# GateDrivers.net
KiCad netlist of a schematic drawn in Altium Designer
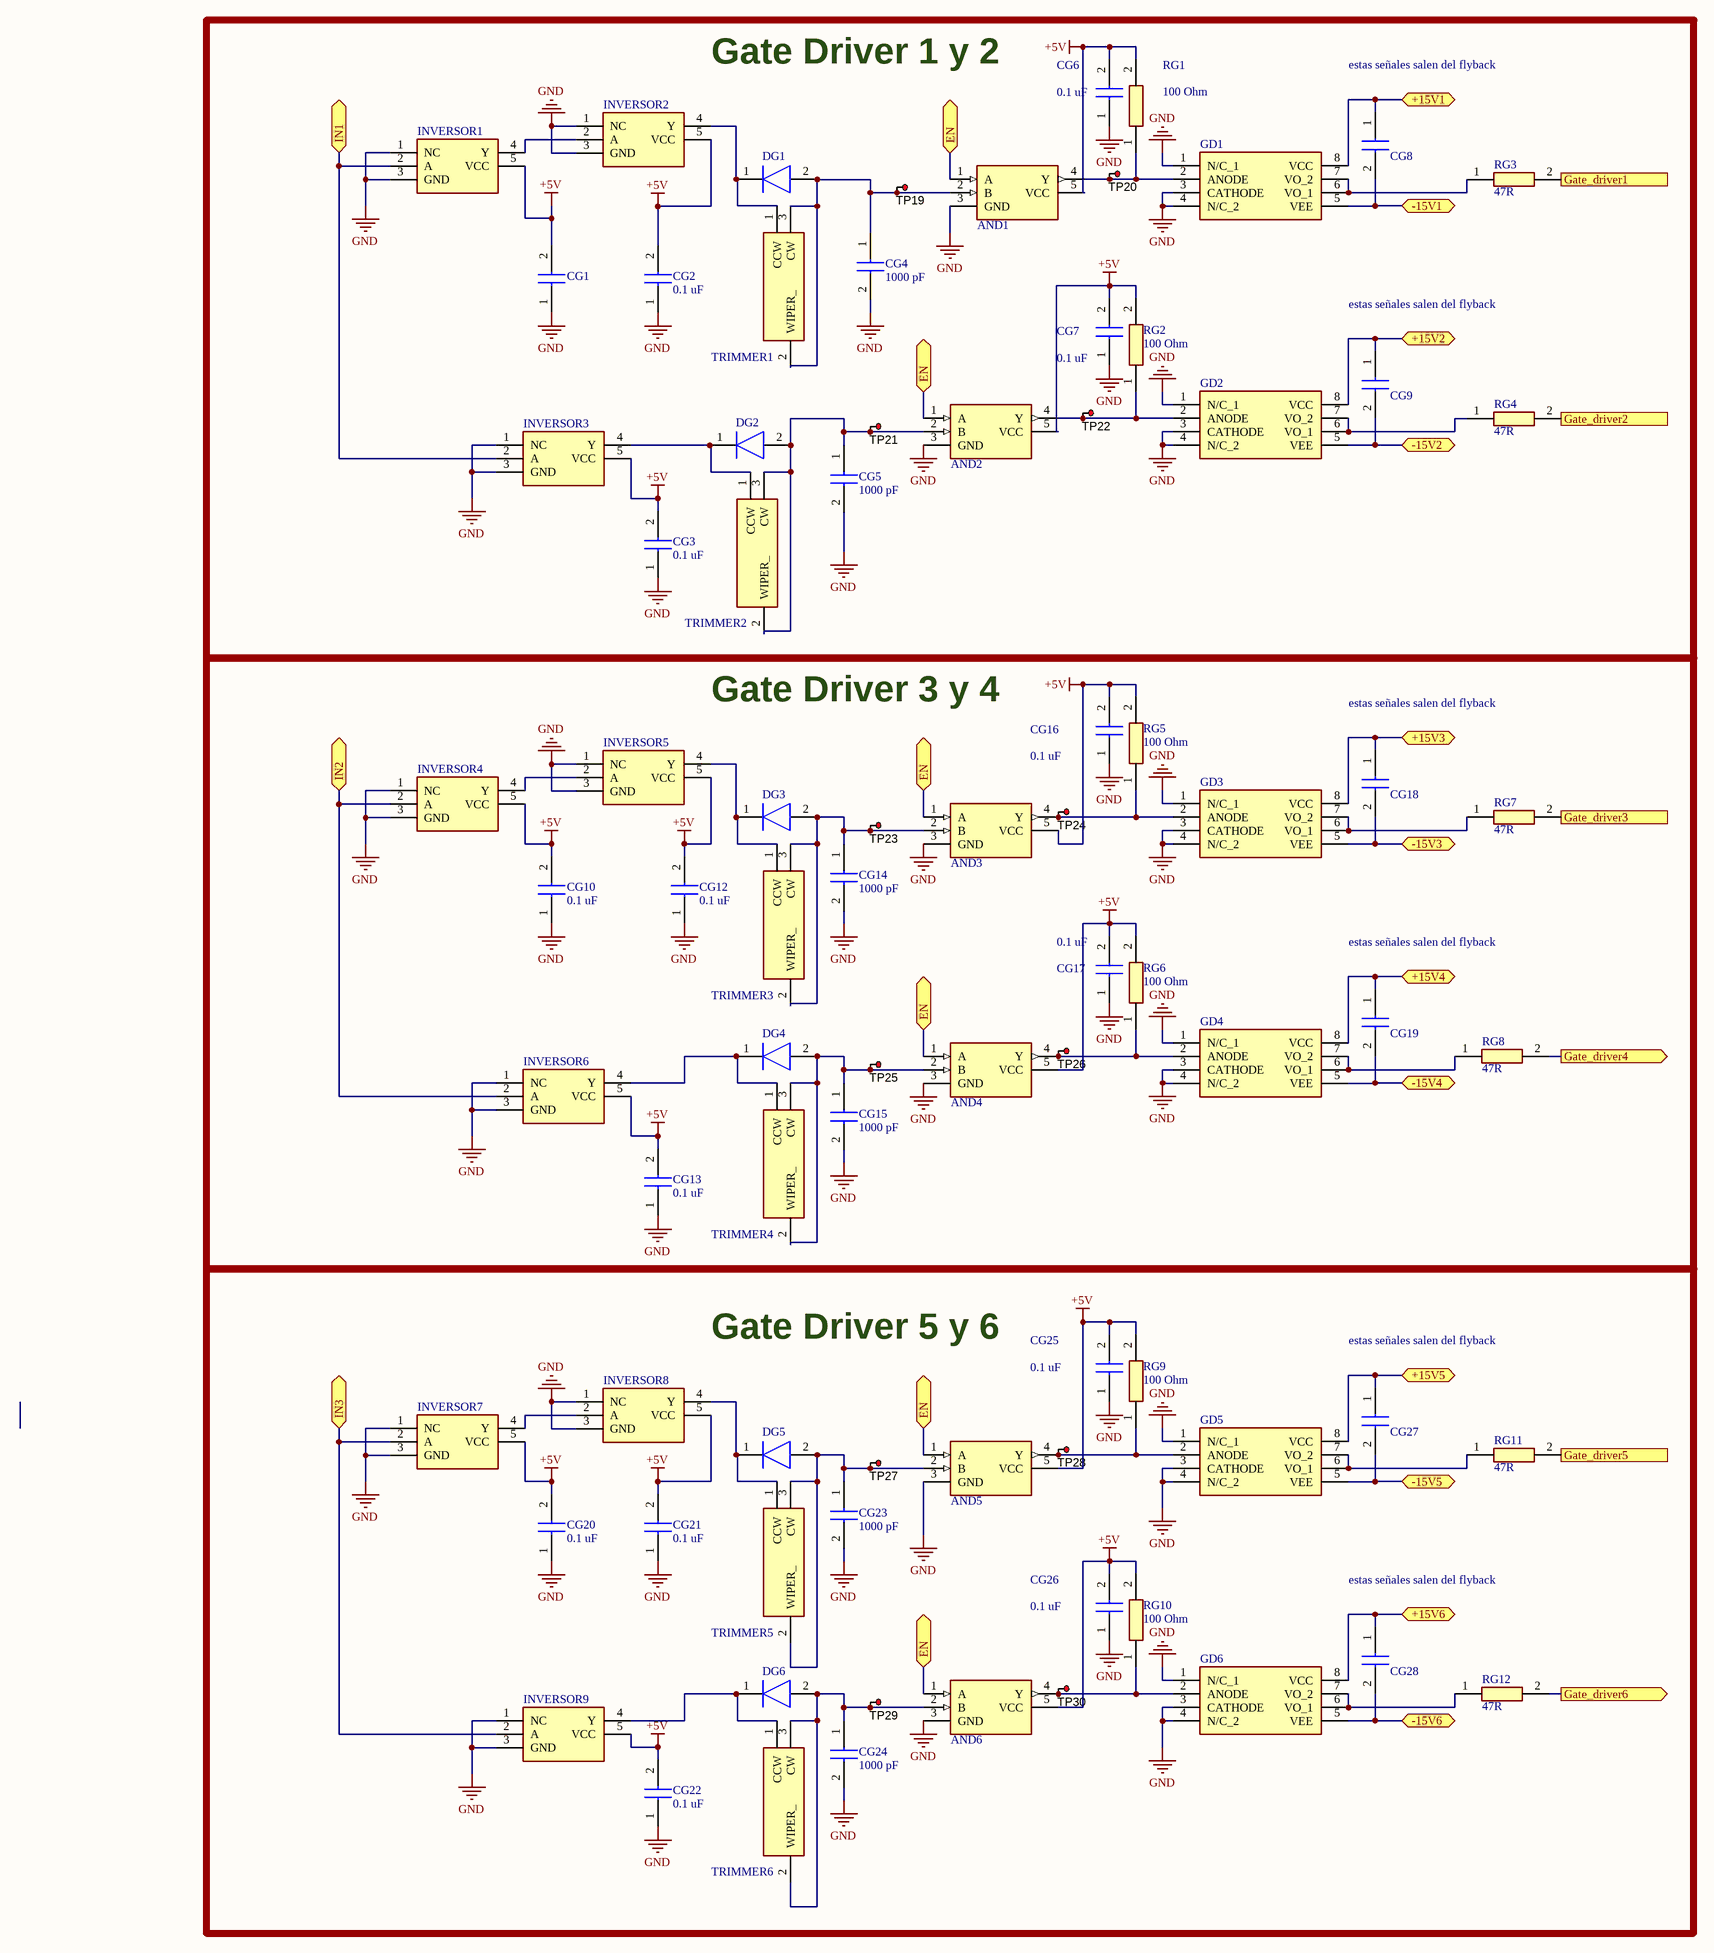
[diagram p0: GateDrivers.SchDoc]

(export (version "E")
  (design (tool "Eeschema 10.0.6"))
  (components
    (comp (ref "AND1")
      (value "SN74AHC1G09DCKR")
      (footprint "jasiel:SOT65P210X110-5N")
      (fields (field (name "MANUFACTURER") "Texas Instruments"))
      (libsource (lib "sch jasiel") (part "SN74AHC1G09DCKR"))
    )
    (comp (ref "AND2")
      (value "SN74AHC1G09DCKR")
      (footprint "jasiel:SOT65P210X110-5N")
      (fields (field (name "MANUFACTURER") "Texas Instruments"))
      (libsource (lib "sch jasiel") (part "SN74AHC1G09DCKR"))
    )
    (comp (ref "AND3")
      (value "SN74AHC1G09DCKR")
      (footprint "jasiel:SOT65P210X110-5N")
      (fields (field (name "MANUFACTURER") "Texas Instruments"))
      (libsource (lib "sch jasiel") (part "SN74AHC1G09DCKR"))
    )
    (comp (ref "AND4")
      (value "SN74AHC1G09DCKR")
      (footprint "jasiel:SOT65P210X110-5N")
      (fields (field (name "MANUFACTURER") "Texas Instruments"))
      (libsource (lib "sch jasiel") (part "SN74AHC1G09DCKR"))
    )
    (comp (ref "AND5")
      (value "SN74AHC1G09DCKR")
      (footprint "jasiel:SOT65P210X110-5N")
      (fields (field (name "MANUFACTURER") "Texas Instruments"))
      (libsource (lib "sch jasiel") (part "SN74AHC1G09DCKR"))
    )
    (comp (ref "AND6")
      (value "SN74AHC1G09DCKR")
      (footprint "jasiel:SOT65P210X110-5N")
      (fields (field (name "MANUFACTURER") "Texas Instruments"))
      (libsource (lib "sch jasiel") (part "SN74AHC1G09DCKR"))
    )
    (comp (ref "CG1")
      (value "~")
      (footprint "SamacSys:CAPC2012X94N")
      (description "Multilayer Ceramic Capacitors MLCC - SMD/SMT 16V .1uF X7R 0805 10%")
      (fields
        (field (name "MANUFACTURER_PART_NUMBER") "0805YC104KAT2A")
        (field (name "MOUSER PART NUMBER") "581-0805YC104K")
      )
      (libsource (lib "sch jasiel") (part "0805YC104KAT2A"))
    )
    (comp (ref "CG2")
      (value "0.1 uF")
      (footprint "SamacSys:CAPC2012X94N")
      (description "Multilayer Ceramic Capacitors MLCC - SMD/SMT 16V .1uF X7R 0805 10%")
      (fields
        (field (name "MANUFACTURER_PART_NUMBER") "0805YC104KAT2A")
        (field (name "MOUSER PART NUMBER") "581-0805YC104K")
      )
      (libsource (lib "*") (part "0805YC104KAT2A"))
    )
    (comp (ref "CG3")
      (value "0.1 uF")
      (footprint "SamacSys:CAPC2012X94N")
      (description "Multilayer Ceramic Capacitors MLCC - SMD/SMT 16V .1uF X7R 0805 10%")
      (fields
        (field (name "MANUFACTURER_PART_NUMBER") "0805YC104KAT2A")
        (field (name "MOUSER PART NUMBER") "581-0805YC104K")
      )
      (libsource (lib "*") (part "0805YC104KAT2A"))
    )
    (comp (ref "CG4")
      (value "1000 pF")
      (footprint "SamacSys:CAPC2012X98N")
      (description "Multilayer Ceramic Capacitors MLCC - SMD/SMT 25volts 1000pF 10% X7R")
      (fields
        (field (name "MANUFACTURER_PART_NUMBER") "C0805Y102K3RACTU")
        (field (name "MOUSER PART NUMBER") "80-C0805Y102K3R")
      )
      (libsource (lib "sch jasiel") (part "C0805Y102K3RACTU"))
    )
    (comp (ref "CG5")
      (value "1000 pF")
      (footprint "SamacSys:CAPC2012X98N")
      (description "Multilayer Ceramic Capacitors MLCC - SMD/SMT 25volts 1000pF 10% X7R")
      (fields
        (field (name "MANUFACTURER_PART_NUMBER") "C0805Y102K3RACTU")
        (field (name "MOUSER PART NUMBER") "80-C0805Y102K3R")
      )
      (libsource (lib "sch jasiel") (part "C0805Y102K3RACTU"))
    )
    (comp (ref "CG6")
      (value "0.1 uF")
      (footprint "SamacSys:CAPC2012X94N")
      (description "Multilayer Ceramic Capacitors MLCC - SMD/SMT 16V .1uF X7R 0805 10%")
      (fields
        (field (name "MANUFACTURER_PART_NUMBER") "0805YC104KAT2A")
        (field (name "MOUSER PART NUMBER") "581-0805YC104K")
      )
      (libsource (lib "*") (part "0805YC104KAT2A"))
    )
    (comp (ref "CG7")
      (value "0.1 uF")
      (footprint "SamacSys:CAPC2012X94N")
      (description "Multilayer Ceramic Capacitors MLCC - SMD/SMT 16V .1uF X7R 0805 10%")
      (fields
        (field (name "MANUFACTURER_PART_NUMBER") "0805YC104KAT2A")
        (field (name "MOUSER PART NUMBER") "581-0805YC104K")
      )
      (libsource (lib "*") (part "0805YC104KAT2A"))
    )
    (comp (ref "CG8")
      (value "CGA2B3X7R1V104M050BB_1")
      (footprint "jasiel:CAPC1005X55N")
      (description "Cap Ceramic 0.1uF 35V X7R 20% Pad SMD 0402 125C Automotive T/R")
      (fields
        (field (name "MANUFACTURER_PART_NUMBER") "CGA2B3X7R1V104M050BB")
        (field (name "MANUFACTURER") "TDK")
      )
      (libsource (lib "sch jasiel") (part "CGA2B3X7R1V104M050BB_1"))
    )
    (comp (ref "CG9")
      (value "CGA2B3X7R1V104M050BB_1")
      (footprint "jasiel:CAPC1005X55N")
      (description "Cap Ceramic 0.1uF 35V X7R 20% Pad SMD 0402 125C Automotive T/R")
      (fields
        (field (name "MANUFACTURER_PART_NUMBER") "CGA2B3X7R1V104M050BB")
        (field (name "MANUFACTURER") "TDK")
      )
      (libsource (lib "sch jasiel") (part "CGA2B3X7R1V104M050BB_1"))
    )
    (comp (ref "CG10")
      (value "0.1 uF")
      (footprint "SamacSys:CAPC2012X94N")
      (description "Multilayer Ceramic Capacitors MLCC - SMD/SMT 16V .1uF X7R 0805 10%")
      (fields
        (field (name "MANUFACTURER_PART_NUMBER") "0805YC104KAT2A")
        (field (name "MOUSER PART NUMBER") "581-0805YC104K")
      )
      (libsource (lib "*") (part "0805YC104KAT2A"))
    )
    (comp (ref "CG12")
      (value "0.1 uF")
      (footprint "SamacSys:CAPC2012X94N")
      (description "Multilayer Ceramic Capacitors MLCC - SMD/SMT 16V .1uF X7R 0805 10%")
      (fields
        (field (name "MANUFACTURER_PART_NUMBER") "0805YC104KAT2A")
        (field (name "MOUSER PART NUMBER") "581-0805YC104K")
      )
      (libsource (lib "*") (part "0805YC104KAT2A"))
    )
    (comp (ref "CG13")
      (value "0.1 uF")
      (footprint "SamacSys:CAPC2012X94N")
      (description "Multilayer Ceramic Capacitors MLCC - SMD/SMT 16V .1uF X7R 0805 10%")
      (fields
        (field (name "MANUFACTURER_PART_NUMBER") "0805YC104KAT2A")
        (field (name "MOUSER PART NUMBER") "581-0805YC104K")
      )
      (libsource (lib "*") (part "0805YC104KAT2A"))
    )
    (comp (ref "CG14")
      (value "1000 pF")
      (footprint "SamacSys:CAPC2012X98N")
      (description "Multilayer Ceramic Capacitors MLCC - SMD/SMT 25volts 1000pF 10% X7R")
      (fields
        (field (name "MANUFACTURER_PART_NUMBER") "C0805Y102K3RACTU")
        (field (name "MOUSER PART NUMBER") "80-C0805Y102K3R")
      )
      (libsource (lib "sch jasiel") (part "C0805Y102K3RACTU"))
    )
    (comp (ref "CG15")
      (value "1000 pF")
      (footprint "SamacSys:CAPC2012X98N")
      (description "Multilayer Ceramic Capacitors MLCC - SMD/SMT 25volts 1000pF 10% X7R")
      (fields
        (field (name "MANUFACTURER_PART_NUMBER") "C0805Y102K3RACTU")
        (field (name "MOUSER PART NUMBER") "80-C0805Y102K3R")
      )
      (libsource (lib "sch jasiel") (part "C0805Y102K3RACTU"))
    )
    (comp (ref "CG16")
      (value "0.1 uF")
      (footprint "SamacSys:CAPC2012X94N")
      (description "Multilayer Ceramic Capacitors MLCC - SMD/SMT 16V .1uF X7R 0805 10%")
      (fields
        (field (name "MANUFACTURER_PART_NUMBER") "0805YC104KAT2A")
        (field (name "MOUSER PART NUMBER") "581-0805YC104K")
      )
      (libsource (lib "*") (part "0805YC104KAT2A"))
    )
    (comp (ref "CG17")
      (value "0.1 uF")
      (footprint "SamacSys:CAPC2012X94N")
      (description "Multilayer Ceramic Capacitors MLCC - SMD/SMT 16V .1uF X7R 0805 10%")
      (fields
        (field (name "MANUFACTURER_PART_NUMBER") "0805YC104KAT2A")
        (field (name "MOUSER PART NUMBER") "581-0805YC104K")
      )
      (libsource (lib "*") (part "0805YC104KAT2A"))
    )
    (comp (ref "CG18")
      (value "CGA2B3X7R1V104M050BB_1")
      (footprint "jasiel:CAPC1005X55N")
      (description "Cap Ceramic 0.1uF 35V X7R 20% Pad SMD 0402 125C Automotive T/R")
      (fields
        (field (name "MANUFACTURER_PART_NUMBER") "CGA2B3X7R1V104M050BB")
        (field (name "MANUFACTURER") "TDK")
      )
      (libsource (lib "sch jasiel") (part "CGA2B3X7R1V104M050BB_1"))
    )
    (comp (ref "CG19")
      (value "CGA2B3X7R1V104M050BB_1")
      (footprint "jasiel:CAPC1005X55N")
      (description "Cap Ceramic 0.1uF 35V X7R 20% Pad SMD 0402 125C Automotive T/R")
      (fields
        (field (name "MANUFACTURER_PART_NUMBER") "CGA2B3X7R1V104M050BB")
        (field (name "MANUFACTURER") "TDK")
      )
      (libsource (lib "sch jasiel") (part "CGA2B3X7R1V104M050BB_1"))
    )
    (comp (ref "CG20")
      (value "0.1 uF")
      (footprint "SamacSys:CAPC2012X94N")
      (description "Multilayer Ceramic Capacitors MLCC - SMD/SMT 16V .1uF X7R 0805 10%")
      (fields
        (field (name "MANUFACTURER_PART_NUMBER") "0805YC104KAT2A")
        (field (name "MOUSER PART NUMBER") "581-0805YC104K")
      )
      (libsource (lib "*") (part "0805YC104KAT2A"))
    )
    (comp (ref "CG21")
      (value "0.1 uF")
      (footprint "SamacSys:CAPC2012X94N")
      (description "Multilayer Ceramic Capacitors MLCC - SMD/SMT 16V .1uF X7R 0805 10%")
      (fields
        (field (name "MANUFACTURER_PART_NUMBER") "0805YC104KAT2A")
        (field (name "MOUSER PART NUMBER") "581-0805YC104K")
      )
      (libsource (lib "*") (part "0805YC104KAT2A"))
    )
    (comp (ref "CG22")
      (value "0.1 uF")
      (footprint "SamacSys:CAPC2012X94N")
      (description "Multilayer Ceramic Capacitors MLCC - SMD/SMT 16V .1uF X7R 0805 10%")
      (fields
        (field (name "MANUFACTURER_PART_NUMBER") "0805YC104KAT2A")
        (field (name "MOUSER PART NUMBER") "581-0805YC104K")
      )
      (libsource (lib "*") (part "0805YC104KAT2A"))
    )
    (comp (ref "CG23")
      (value "1000 pF")
      (footprint "SamacSys:CAPC2012X98N")
      (description "Multilayer Ceramic Capacitors MLCC - SMD/SMT 25volts 1000pF 10% X7R")
      (fields
        (field (name "MANUFACTURER_PART_NUMBER") "C0805Y102K3RACTU")
        (field (name "MOUSER PART NUMBER") "80-C0805Y102K3R")
      )
      (libsource (lib "sch jasiel") (part "C0805Y102K3RACTU"))
    )
    (comp (ref "CG24")
      (value "1000 pF")
      (footprint "SamacSys:CAPC2012X98N")
      (description "Multilayer Ceramic Capacitors MLCC - SMD/SMT 25volts 1000pF 10% X7R")
      (fields
        (field (name "MANUFACTURER_PART_NUMBER") "C0805Y102K3RACTU")
        (field (name "MOUSER PART NUMBER") "80-C0805Y102K3R")
      )
      (libsource (lib "sch jasiel") (part "C0805Y102K3RACTU"))
    )
    (comp (ref "CG25")
      (value "0.1 uF")
      (footprint "SamacSys:CAPC2012X94N")
      (description "Multilayer Ceramic Capacitors MLCC - SMD/SMT 16V .1uF X7R 0805 10%")
      (fields
        (field (name "MANUFACTURER_PART_NUMBER") "0805YC104KAT2A")
        (field (name "MOUSER PART NUMBER") "581-0805YC104K")
      )
      (libsource (lib "*") (part "0805YC104KAT2A"))
    )
    (comp (ref "CG26")
      (value "0.1 uF")
      (footprint "SamacSys:CAPC2012X94N")
      (description "Multilayer Ceramic Capacitors MLCC - SMD/SMT 16V .1uF X7R 0805 10%")
      (fields
        (field (name "MANUFACTURER_PART_NUMBER") "0805YC104KAT2A")
        (field (name "MOUSER PART NUMBER") "581-0805YC104K")
      )
      (libsource (lib "*") (part "0805YC104KAT2A"))
    )
    (comp (ref "CG27")
      (value "CGA2B3X7R1V104M050BB_1")
      (footprint "jasiel:CAPC1005X55N")
      (description "Cap Ceramic 0.1uF 35V X7R 20% Pad SMD 0402 125C Automotive T/R")
      (fields
        (field (name "MANUFACTURER_PART_NUMBER") "CGA2B3X7R1V104M050BB")
        (field (name "MANUFACTURER") "TDK")
      )
      (libsource (lib "sch jasiel") (part "CGA2B3X7R1V104M050BB_1"))
    )
    (comp (ref "CG28")
      (value "CGA2B3X7R1V104M050BB_1")
      (footprint "jasiel:CAPC1005X55N")
      (description "Cap Ceramic 0.1uF 35V X7R 20% Pad SMD 0402 125C Automotive T/R")
      (fields
        (field (name "MANUFACTURER_PART_NUMBER") "CGA2B3X7R1V104M050BB")
        (field (name "MANUFACTURER") "TDK")
      )
      (libsource (lib "sch jasiel") (part "CGA2B3X7R1V104M050BB_1"))
    )
    (comp (ref "DG1")
      (value "BAS85-GS08")
      (footprint "jasiel:BAQ33GS08")
      (description "VISHAY - BAS85-GS08 - Small Signal Schottky Diode, Single, 30 V, 200 mA, 800 mV, 600 mA, 125 °C")
      (fields (field (name "MANUFACTURER") "Vishay Semiconductors") (field (name "VOLTAGE") "30V"))
      (libsource (lib "sch jasiel") (part "BAS85-GS08"))
    )
    (comp (ref "DG2")
      (value "BAS85-GS08")
      (footprint "jasiel:BAQ33GS08")
      (description "VISHAY - BAS85-GS08 - Small Signal Schottky Diode, Single, 30 V, 200 mA, 800 mV, 600 mA, 125 °C")
      (fields (field (name "MANUFACTURER") "Vishay Semiconductors") (field (name "VOLTAGE") "30V"))
      (libsource (lib "sch jasiel") (part "BAS85-GS08"))
    )
    (comp (ref "DG3")
      (value "BAS85-GS08")
      (footprint "jasiel:BAQ33GS08")
      (description "VISHAY - BAS85-GS08 - Small Signal Schottky Diode, Single, 30 V, 200 mA, 800 mV, 600 mA, 125 °C")
      (fields (field (name "MANUFACTURER") "Vishay Semiconductors") (field (name "VOLTAGE") "30V"))
      (libsource (lib "sch jasiel") (part "BAS85-GS08"))
    )
    (comp (ref "DG4")
      (value "BAS85-GS08")
      (footprint "jasiel:BAQ33GS08")
      (description "VISHAY - BAS85-GS08 - Small Signal Schottky Diode, Single, 30 V, 200 mA, 800 mV, 600 mA, 125 °C")
      (fields (field (name "MANUFACTURER") "Vishay Semiconductors") (field (name "VOLTAGE") "30V"))
      (libsource (lib "sch jasiel") (part "BAS85-GS08"))
    )
    (comp (ref "DG5")
      (value "BAS85-GS08")
      (footprint "jasiel:BAQ33GS08")
      (description "VISHAY - BAS85-GS08 - Small Signal Schottky Diode, Single, 30 V, 200 mA, 800 mV, 600 mA, 125 °C")
      (fields (field (name "MANUFACTURER") "Vishay Semiconductors") (field (name "VOLTAGE") "30V"))
      (libsource (lib "sch jasiel") (part "BAS85-GS08"))
    )
    (comp (ref "DG6")
      (value "BAS85-GS08")
      (footprint "jasiel:BAQ33GS08")
      (description "VISHAY - BAS85-GS08 - Small Signal Schottky Diode, Single, 30 V, 200 mA, 800 mV, 600 mA, 125 °C")
      (fields (field (name "MANUFACTURER") "Vishay Semiconductors") (field (name "VOLTAGE") "30V"))
      (libsource (lib "sch jasiel") (part "BAS85-GS08"))
    )
    (comp (ref "GD1")
      (value "HCPL-3120")
      (footprint "jasiel:DIP762W65P254L965H470Q8N")
      (description "Optocoupler Drive Push-Pull 1-CH 30V 1500V 8-Pin PDIP")
      (fields
        (field (name "MOUSER2 PART NUMBER") "630-HCPL-3120")
        (field (name "MANUFACTURER") "Broadcom Avago")
      )
      (libsource (lib "sch jasiel") (part "HCPL-3120"))
    )
    (comp (ref "GD2")
      (value "HCPL-3120")
      (footprint "jasiel:DIP762W65P254L965H470Q8N")
      (description "Optocoupler Drive Push-Pull 1-CH 30V 1500V 8-Pin PDIP")
      (fields
        (field (name "MOUSER2 PART NUMBER") "630-HCPL-3120")
        (field (name "MANUFACTURER") "Broadcom Avago")
      )
      (libsource (lib "sch jasiel") (part "HCPL-3120"))
    )
    (comp (ref "GD3")
      (value "HCPL-3120")
      (footprint "jasiel:DIP762W65P254L965H470Q8N")
      (description "Optocoupler Drive Push-Pull 1-CH 30V 1500V 8-Pin PDIP")
      (fields
        (field (name "MOUSER2 PART NUMBER") "630-HCPL-3120")
        (field (name "MANUFACTURER") "Broadcom Avago")
      )
      (libsource (lib "sch jasiel") (part "HCPL-3120"))
    )
    (comp (ref "GD4")
      (value "HCPL-3120")
      (footprint "jasiel:DIP762W65P254L965H470Q8N")
      (description "Optocoupler Drive Push-Pull 1-CH 30V 1500V 8-Pin PDIP")
      (fields
        (field (name "MOUSER2 PART NUMBER") "630-HCPL-3120")
        (field (name "MANUFACTURER") "Broadcom Avago")
      )
      (libsource (lib "sch jasiel") (part "HCPL-3120"))
    )
    (comp (ref "GD5")
      (value "HCPL-3120")
      (footprint "jasiel:DIP762W65P254L965H470Q8N")
      (description "Optocoupler Drive Push-Pull 1-CH 30V 1500V 8-Pin PDIP")
      (fields
        (field (name "MOUSER2 PART NUMBER") "630-HCPL-3120")
        (field (name "MANUFACTURER") "Broadcom Avago")
      )
      (libsource (lib "sch jasiel") (part "HCPL-3120"))
    )
    (comp (ref "GD6")
      (value "HCPL-3120")
      (footprint "jasiel:DIP762W65P254L965H470Q8N")
      (description "Optocoupler Drive Push-Pull 1-CH 30V 1500V 8-Pin PDIP")
      (fields
        (field (name "MOUSER2 PART NUMBER") "630-HCPL-3120")
        (field (name "MANUFACTURER") "Broadcom Avago")
      )
      (libsource (lib "sch jasiel") (part "HCPL-3120"))
    )
    (comp (ref "INVERSOR1")
      (value "SN74AHC1G14DRLR")
      (footprint "SamacSys:SOTFL50P160X60-5N")
      (description "IC INVERTER SCHMITT 1CH SOT5")
      (fields
        (field (name "MOUSER2 PART NUMBER") "595-SN74AHC1G14DRLR")
        (field (name "MANUFACTURER") "Texas Instruments")
      )
      (libsource (lib "sch jasiel") (part "SN74AHC1G14DRLR"))
    )
    (comp (ref "INVERSOR2")
      (value "SN74AHC1G14DRLR")
      (footprint "SamacSys:SOTFL50P160X60-5N")
      (description "IC INVERTER SCHMITT 1CH SOT5")
      (fields
        (field (name "MOUSER2 PART NUMBER") "595-SN74AHC1G14DRLR")
        (field (name "MANUFACTURER") "Texas Instruments")
      )
      (libsource (lib "sch jasiel") (part "SN74AHC1G14DRLR"))
    )
    (comp (ref "INVERSOR3")
      (value "SN74AHC1G14DRLR")
      (footprint "SamacSys:SOTFL50P160X60-5N")
      (description "IC INVERTER SCHMITT 1CH SOT5")
      (fields
        (field (name "MOUSER2 PART NUMBER") "595-SN74AHC1G14DRLR")
        (field (name "MANUFACTURER") "Texas Instruments")
      )
      (libsource (lib "sch jasiel") (part "SN74AHC1G14DRLR"))
    )
    (comp (ref "INVERSOR4")
      (value "SN74AHC1G14DRLR")
      (footprint "SamacSys:SOTFL50P160X60-5N")
      (description "IC INVERTER SCHMITT 1CH SOT5")
      (fields
        (field (name "MOUSER2 PART NUMBER") "595-SN74AHC1G14DRLR")
        (field (name "MANUFACTURER") "Texas Instruments")
      )
      (libsource (lib "sch jasiel") (part "SN74AHC1G14DRLR"))
    )
    (comp (ref "INVERSOR5")
      (value "SN74AHC1G14DRLR")
      (footprint "SamacSys:SOTFL50P160X60-5N")
      (description "IC INVERTER SCHMITT 1CH SOT5")
      (fields
        (field (name "MOUSER2 PART NUMBER") "595-SN74AHC1G14DRLR")
        (field (name "MANUFACTURER") "Texas Instruments")
      )
      (libsource (lib "sch jasiel") (part "SN74AHC1G14DRLR"))
    )
    (comp (ref "INVERSOR6")
      (value "SN74AHC1G14DRLR")
      (footprint "SamacSys:SOTFL50P160X60-5N")
      (description "IC INVERTER SCHMITT 1CH SOT5")
      (fields
        (field (name "MOUSER2 PART NUMBER") "595-SN74AHC1G14DRLR")
        (field (name "MANUFACTURER") "Texas Instruments")
      )
      (libsource (lib "sch jasiel") (part "SN74AHC1G14DRLR"))
    )
    (comp (ref "INVERSOR7")
      (value "SN74AHC1G14DRLR")
      (footprint "SamacSys:SOTFL50P160X60-5N")
      (description "IC INVERTER SCHMITT 1CH SOT5")
      (fields
        (field (name "MOUSER2 PART NUMBER") "595-SN74AHC1G14DRLR")
        (field (name "MANUFACTURER") "Texas Instruments")
      )
      (libsource (lib "sch jasiel") (part "SN74AHC1G14DRLR"))
    )
    (comp (ref "INVERSOR8")
      (value "SN74AHC1G14DRLR")
      (footprint "SamacSys:SOTFL50P160X60-5N")
      (description "IC INVERTER SCHMITT 1CH SOT5")
      (fields
        (field (name "MOUSER2 PART NUMBER") "595-SN74AHC1G14DRLR")
        (field (name "MANUFACTURER") "Texas Instruments")
      )
      (libsource (lib "sch jasiel") (part "SN74AHC1G14DRLR"))
    )
    (comp (ref "INVERSOR9")
      (value "SN74AHC1G14DRLR")
      (footprint "SamacSys:SOTFL50P160X60-5N")
      (description "IC INVERTER SCHMITT 1CH SOT5")
      (fields
        (field (name "MOUSER2 PART NUMBER") "595-SN74AHC1G14DRLR")
        (field (name "MANUFACTURER") "Texas Instruments")
      )
      (libsource (lib "sch jasiel") (part "SN74AHC1G14DRLR"))
    )
    (comp (ref "RG1")
      (value "100 Ohm")
      (footprint "jasiel:RESC1608X55N")
      (description "YAGEO - RC0603JR-13100RL - RES, THICK FILM, 100R, 5%, 0.1W, 0603")
      (fields
        (field (name "MANUFACTURER_PART_NUMBER") "RC0603JR-13100RL")
        (field (name "MANUFACTURER") "Yageo")
      )
      (libsource (lib "sch jasiel") (part "RC0603JR-13100RL"))
    )
    (comp (ref "RG2")
      (value "100 Ohm")
      (footprint "jasiel:RESC1608X55N")
      (description "YAGEO - RC0603JR-13100RL - RES, THICK FILM, 100R, 5%, 0.1W, 0603")
      (fields
        (field (name "MANUFACTURER_PART_NUMBER") "RC0603JR-13100RL")
        (field (name "MANUFACTURER") "Yageo")
      )
      (libsource (lib "sch jasiel") (part "RC0603JR-13100RL"))
    )
    (comp (ref "RG3")
      (value "RCL121847R0JNEK_1")
      (footprint "SamacSys:RESC3246X60N")
      (description "Res Thick Film 1218 47 Ohm 5% 1W ±200ppm/C Pad SMD Automotive T/R")
      (fields
        (field (name "MANUFACTURER_PART_NUMBER") "RCL121847R0JNEK")
        (field (name "MANUFACTURER") "Vishay")
        (field (name "RESISTANCE") "47R")
      )
      (libsource (lib "sch jasiel") (part "RCL121847R0JNEK_1"))
    )
    (comp (ref "RG4")
      (value "RCL121847R0JNEK_1")
      (footprint "SamacSys:RESC3246X60N")
      (description "Res Thick Film 1218 47 Ohm 5% 1W ±200ppm/C Pad SMD Automotive T/R")
      (fields
        (field (name "MANUFACTURER_PART_NUMBER") "RCL121847R0JNEK")
        (field (name "MANUFACTURER") "Vishay")
        (field (name "RESISTANCE") "47R")
      )
      (libsource (lib "sch jasiel") (part "RCL121847R0JNEK_1"))
    )
    (comp (ref "RG5")
      (value "100 Ohm")
      (footprint "jasiel:RESC1608X55N")
      (description "YAGEO - RC0603JR-13100RL - RES, THICK FILM, 100R, 5%, 0.1W, 0603")
      (fields
        (field (name "MANUFACTURER_PART_NUMBER") "RC0603JR-13100RL")
        (field (name "MANUFACTURER") "Yageo")
      )
      (libsource (lib "sch jasiel") (part "RC0603JR-13100RL"))
    )
    (comp (ref "RG6")
      (value "100 Ohm")
      (footprint "jasiel:RESC1608X55N")
      (description "YAGEO - RC0603JR-13100RL - RES, THICK FILM, 100R, 5%, 0.1W, 0603")
      (fields
        (field (name "MANUFACTURER_PART_NUMBER") "RC0603JR-13100RL")
        (field (name "MANUFACTURER") "Yageo")
      )
      (libsource (lib "sch jasiel") (part "RC0603JR-13100RL"))
    )
    (comp (ref "RG7")
      (value "RCL121847R0JNEK_1")
      (footprint "SamacSys:RESC3246X60N")
      (description "Res Thick Film 1218 47 Ohm 5% 1W ±200ppm/C Pad SMD Automotive T/R")
      (fields
        (field (name "MANUFACTURER_PART_NUMBER") "RCL121847R0JNEK")
        (field (name "MANUFACTURER") "Vishay")
        (field (name "RESISTANCE") "47R")
      )
      (libsource (lib "sch jasiel") (part "RCL121847R0JNEK_1"))
    )
    (comp (ref "RG8")
      (value "RCL121847R0JNEK_1")
      (footprint "SamacSys:RESC3246X60N")
      (description "Res Thick Film 1218 47 Ohm 5% 1W ±200ppm/C Pad SMD Automotive T/R")
      (fields
        (field (name "MANUFACTURER_PART_NUMBER") "RCL121847R0JNEK")
        (field (name "MANUFACTURER") "Vishay")
        (field (name "RESISTANCE") "47R")
      )
      (libsource (lib "sch jasiel") (part "RCL121847R0JNEK_1"))
    )
    (comp (ref "RG9")
      (value "100 Ohm")
      (footprint "jasiel:RESC1608X55N")
      (description "YAGEO - RC0603JR-13100RL - RES, THICK FILM, 100R, 5%, 0.1W, 0603")
      (fields
        (field (name "MANUFACTURER_PART_NUMBER") "RC0603JR-13100RL")
        (field (name "MANUFACTURER") "Yageo")
      )
      (libsource (lib "sch jasiel") (part "RC0603JR-13100RL"))
    )
    (comp (ref "RG10")
      (value "100 Ohm")
      (footprint "jasiel:RESC1608X55N")
      (description "YAGEO - RC0603JR-13100RL - RES, THICK FILM, 100R, 5%, 0.1W, 0603")
      (fields
        (field (name "MANUFACTURER_PART_NUMBER") "RC0603JR-13100RL")
        (field (name "MANUFACTURER") "Yageo")
      )
      (libsource (lib "sch jasiel") (part "RC0603JR-13100RL"))
    )
    (comp (ref "RG11")
      (value "RCL121847R0JNEK_1")
      (footprint "SamacSys:RESC3246X60N")
      (description "Res Thick Film 1218 47 Ohm 5% 1W ±200ppm/C Pad SMD Automotive T/R")
      (fields
        (field (name "MANUFACTURER_PART_NUMBER") "RCL121847R0JNEK")
        (field (name "MANUFACTURER") "Vishay")
        (field (name "RESISTANCE") "47R")
      )
      (libsource (lib "sch jasiel") (part "RCL121847R0JNEK_1"))
    )
    (comp (ref "RG12")
      (value "RCL121847R0JNEK_1")
      (footprint "SamacSys:RESC3246X60N")
      (description "Res Thick Film 1218 47 Ohm 5% 1W ±200ppm/C Pad SMD Automotive T/R")
      (fields
        (field (name "MANUFACTURER_PART_NUMBER") "RCL121847R0JNEK")
        (field (name "MANUFACTURER") "Vishay")
        (field (name "RESISTANCE") "47R")
      )
      (libsource (lib "sch jasiel") (part "RCL121847R0JNEK_1"))
    )
    (comp (ref "TP19")
      (value "5010")
      (footprint "Keystone5010")
      (description "Test Point, Multipurpose, Red, TH")
      (fields (field (name "MANUFACTURER") "Keystone") (field (name "PUBLISHER") "Texas Instruments"))
      (libsource (lib "sch jasiel") (part "5010"))
    )
    (comp (ref "TP20")
      (value "5010")
      (footprint "Keystone5010")
      (description "Test Point, Multipurpose, Red, TH")
      (fields (field (name "MANUFACTURER") "Keystone") (field (name "PUBLISHER") "Texas Instruments"))
      (libsource (lib "sch jasiel") (part "5010"))
    )
    (comp (ref "TP21")
      (value "5010")
      (footprint "Keystone5010")
      (description "Test Point, Multipurpose, Red, TH")
      (fields (field (name "MANUFACTURER") "Keystone") (field (name "PUBLISHER") "Texas Instruments"))
      (libsource (lib "sch jasiel") (part "5010"))
    )
    (comp (ref "TP22")
      (value "5010")
      (footprint "Keystone5010")
      (description "Test Point, Multipurpose, Red, TH")
      (fields (field (name "MANUFACTURER") "Keystone") (field (name "PUBLISHER") "Texas Instruments"))
      (libsource (lib "sch jasiel") (part "5010"))
    )
    (comp (ref "TP23")
      (value "5010")
      (footprint "Keystone5010")
      (description "Test Point, Multipurpose, Red, TH")
      (fields (field (name "MANUFACTURER") "Keystone") (field (name "PUBLISHER") "Texas Instruments"))
      (libsource (lib "sch jasiel") (part "5010"))
    )
    (comp (ref "TP24")
      (value "5010")
      (footprint "Keystone5010")
      (description "Test Point, Multipurpose, Red, TH")
      (fields (field (name "MANUFACTURER") "Keystone") (field (name "PUBLISHER") "Texas Instruments"))
      (libsource (lib "sch jasiel") (part "5010"))
    )
    (comp (ref "TP25")
      (value "5010")
      (footprint "Keystone5010")
      (description "Test Point, Multipurpose, Red, TH")
      (fields (field (name "MANUFACTURER") "Keystone") (field (name "PUBLISHER") "Texas Instruments"))
      (libsource (lib "sch jasiel") (part "5010"))
    )
    (comp (ref "TP26")
      (value "5010")
      (footprint "Keystone5010")
      (description "Test Point, Multipurpose, Red, TH")
      (fields (field (name "MANUFACTURER") "Keystone") (field (name "PUBLISHER") "Texas Instruments"))
      (libsource (lib "sch jasiel") (part "5010"))
    )
    (comp (ref "TP27")
      (value "5010")
      (footprint "Keystone5010")
      (description "Test Point, Multipurpose, Red, TH")
      (fields (field (name "MANUFACTURER") "Keystone") (field (name "PUBLISHER") "Texas Instruments"))
      (libsource (lib "sch jasiel") (part "5010"))
    )
    (comp (ref "TP28")
      (value "5010")
      (footprint "Keystone5010")
      (description "Test Point, Multipurpose, Red, TH")
      (fields (field (name "MANUFACTURER") "Keystone") (field (name "PUBLISHER") "Texas Instruments"))
      (libsource (lib "sch jasiel") (part "5010"))
    )
    (comp (ref "TP29")
      (value "5010")
      (footprint "Keystone5010")
      (description "Test Point, Multipurpose, Red, TH")
      (fields (field (name "MANUFACTURER") "Keystone") (field (name "PUBLISHER") "Texas Instruments"))
      (libsource (lib "sch jasiel") (part "5010"))
    )
    (comp (ref "TP30")
      (value "5010")
      (footprint "Keystone5010")
      (description "Test Point, Multipurpose, Red, TH")
      (fields (field (name "MANUFACTURER") "Keystone") (field (name "PUBLISHER") "Texas Instruments"))
      (libsource (lib "sch jasiel") (part "5010"))
    )
    (comp (ref "TRIMMER1")
      (value "ST-4ETB203")
      (footprint "SamacSys:ST4ETB203")
      (description "TRIMMER 20K OHM 0.25W SMD")
      (fields
        (field (name "MANUFACTURER") "Nidec Copal")
        (field (name "MANUFACTURER PART NUMBER") "ST4ETB203")
      )
      (libsource (lib "sch jasiel") (part "ST-4ETB203"))
    )
    (comp (ref "TRIMMER2")
      (value "ST-4ETB203")
      (footprint "SamacSys:ST4ETB203")
      (description "TRIMMER 20K OHM 0.25W SMD")
      (fields
        (field (name "MANUFACTURER") "Nidec Copal")
        (field (name "MANUFACTURER PART NUMBER") "ST4ETB203")
      )
      (libsource (lib "sch jasiel") (part "ST-4ETB203"))
    )
    (comp (ref "TRIMMER3")
      (value "ST-4ETB203")
      (footprint "SamacSys:ST4ETB203")
      (description "TRIMMER 20K OHM 0.25W SMD")
      (fields
        (field (name "MANUFACTURER") "Nidec Copal")
        (field (name "MANUFACTURER PART NUMBER") "ST4ETB203")
      )
      (libsource (lib "sch jasiel") (part "ST-4ETB203"))
    )
    (comp (ref "TRIMMER4")
      (value "ST-4ETB203")
      (footprint "SamacSys:ST4ETB203")
      (description "TRIMMER 20K OHM 0.25W SMD")
      (fields
        (field (name "MANUFACTURER") "Nidec Copal")
        (field (name "MANUFACTURER PART NUMBER") "ST4ETB203")
      )
      (libsource (lib "sch jasiel") (part "ST-4ETB203"))
    )
    (comp (ref "TRIMMER5")
      (value "ST-4ETB203")
      (footprint "SamacSys:ST4ETB203")
      (description "TRIMMER 20K OHM 0.25W SMD")
      (fields
        (field (name "MANUFACTURER") "Nidec Copal")
        (field (name "MANUFACTURER PART NUMBER") "ST4ETB203")
      )
      (libsource (lib "sch jasiel") (part "ST-4ETB203"))
    )
    (comp (ref "TRIMMER6")
      (value "ST-4ETB203")
      (footprint "SamacSys:ST4ETB203")
      (description "TRIMMER 20K OHM 0.25W SMD")
      (fields
        (field (name "MANUFACTURER") "Nidec Copal")
        (field (name "MANUFACTURER PART NUMBER") "ST4ETB203")
      )
      (libsource (lib "sch jasiel") (part "ST-4ETB203"))
    )
  )
  (nets
    (net (code "1") (name "+5V") (class "Default")
      (node (ref "AND1") (pin "5") (pinfunction "VCC_5") (pintype "power_in"))
      (node (ref "AND2") (pin "5") (pinfunction "VCC_5") (pintype "power_in"))
      (node (ref "AND3") (pin "5") (pinfunction "VCC_5") (pintype "power_in"))
      (node (ref "AND4") (pin "5") (pinfunction "VCC_5") (pintype "power_in"))
      (node (ref "AND5") (pin "5") (pinfunction "VCC_5") (pintype "power_in"))
      (node (ref "AND6") (pin "5") (pinfunction "VCC_5") (pintype "power_in"))
      (node (ref "CG1") (pin "2") (pinfunction "2_2") (pintype "passive"))
      (node (ref "CG10") (pin "2") (pinfunction "2_2") (pintype "passive"))
      (node (ref "CG12") (pin "2") (pinfunction "2_2") (pintype "passive"))
      (node (ref "CG13") (pin "2") (pinfunction "2_2") (pintype "passive"))
      (node (ref "CG16") (pin "2") (pinfunction "2_2") (pintype "passive"))
      (node (ref "CG17") (pin "2") (pinfunction "2_2") (pintype "passive"))
      (node (ref "CG2") (pin "2") (pinfunction "2_2") (pintype "passive"))
      (node (ref "CG20") (pin "2") (pinfunction "2_2") (pintype "passive"))
      (node (ref "CG21") (pin "2") (pinfunction "2_2") (pintype "passive"))
      (node (ref "CG22") (pin "2") (pinfunction "2_2") (pintype "passive"))
      (node (ref "CG25") (pin "2") (pinfunction "2_2") (pintype "passive"))
      (node (ref "CG26") (pin "2") (pinfunction "2_2") (pintype "passive"))
      (node (ref "CG3") (pin "2") (pinfunction "2_2") (pintype "passive"))
      (node (ref "CG6") (pin "2") (pinfunction "2_2") (pintype "passive"))
      (node (ref "CG7") (pin "2") (pinfunction "2_2") (pintype "passive"))
      (node (ref "INVERSOR1") (pin "5") (pinfunction "VCC_5") (pintype "passive"))
      (node (ref "INVERSOR2") (pin "5") (pinfunction "VCC_5") (pintype "passive"))
      (node (ref "INVERSOR3") (pin "5") (pinfunction "VCC_5") (pintype "passive"))
      (node (ref "INVERSOR4") (pin "5") (pinfunction "VCC_5") (pintype "passive"))
      (node (ref "INVERSOR5") (pin "5") (pinfunction "VCC_5") (pintype "passive"))
      (node (ref "INVERSOR6") (pin "5") (pinfunction "VCC_5") (pintype "passive"))
      (node (ref "INVERSOR7") (pin "5") (pinfunction "VCC_5") (pintype "passive"))
      (node (ref "INVERSOR8") (pin "5") (pinfunction "VCC_5") (pintype "passive"))
      (node (ref "INVERSOR9") (pin "5") (pinfunction "VCC_5") (pintype "passive"))
      (node (ref "RG1") (pin "2") (pinfunction "2_2") (pintype "passive"))
      (node (ref "RG10") (pin "2") (pinfunction "2_2") (pintype "passive"))
      (node (ref "RG2") (pin "2") (pinfunction "2_2") (pintype "passive"))
      (node (ref "RG5") (pin "2") (pinfunction "2_2") (pintype "passive"))
      (node (ref "RG6") (pin "2") (pinfunction "2_2") (pintype "passive"))
      (node (ref "RG9") (pin "2") (pinfunction "2_2") (pintype "passive"))
    )
    (net (code "2") (name "/+15V1") (class "Default")
      (node (ref "CG8") (pin "1") (pinfunction "1_1") (pintype "passive"))
      (node (ref "GD1") (pin "8") (pinfunction "VCC_8") (pintype "passive"))
    )
    (net (code "3") (name "/+15V2") (class "Default")
      (node (ref "CG9") (pin "1") (pinfunction "1_1") (pintype "passive"))
      (node (ref "GD2") (pin "8") (pinfunction "VCC_8") (pintype "passive"))
    )
    (net (code "4") (name "/+15V3") (class "Default")
      (node (ref "CG18") (pin "1") (pinfunction "1_1") (pintype "passive"))
      (node (ref "GD3") (pin "8") (pinfunction "VCC_8") (pintype "passive"))
    )
    (net (code "5") (name "/+15V4") (class "Default")
      (node (ref "CG19") (pin "1") (pinfunction "1_1") (pintype "passive"))
      (node (ref "GD4") (pin "8") (pinfunction "VCC_8") (pintype "passive"))
    )
    (net (code "6") (name "/+15V5") (class "Default")
      (node (ref "CG27") (pin "1") (pinfunction "1_1") (pintype "passive"))
      (node (ref "GD5") (pin "8") (pinfunction "VCC_8") (pintype "passive"))
    )
    (net (code "7") (name "/+15V6") (class "Default")
      (node (ref "CG28") (pin "1") (pinfunction "1_1") (pintype "passive"))
      (node (ref "GD6") (pin "8") (pinfunction "VCC_8") (pintype "passive"))
    )
    (net (code "8") (name "/-15V1") (class "Default")
      (node (ref "CG8") (pin "2") (pinfunction "2_2") (pintype "passive"))
      (node (ref "GD1") (pin "5") (pinfunction "VEE_5") (pintype "passive"))
    )
    (net (code "9") (name "/-15V2") (class "Default")
      (node (ref "CG9") (pin "2") (pinfunction "2_2") (pintype "passive"))
      (node (ref "GD2") (pin "5") (pinfunction "VEE_5") (pintype "passive"))
    )
    (net (code "10") (name "/-15V3") (class "Default")
      (node (ref "CG18") (pin "2") (pinfunction "2_2") (pintype "passive"))
      (node (ref "GD3") (pin "5") (pinfunction "VEE_5") (pintype "passive"))
    )
    (net (code "11") (name "/-15V4") (class "Default")
      (node (ref "CG19") (pin "2") (pinfunction "2_2") (pintype "passive"))
      (node (ref "GD4") (pin "5") (pinfunction "VEE_5") (pintype "passive"))
    )
    (net (code "12") (name "/-15V5") (class "Default")
      (node (ref "CG27") (pin "2") (pinfunction "2_2") (pintype "passive"))
      (node (ref "GD5") (pin "5") (pinfunction "VEE_5") (pintype "passive"))
    )
    (net (code "13") (name "/-15V6") (class "Default")
      (node (ref "CG28") (pin "2") (pinfunction "2_2") (pintype "passive"))
      (node (ref "GD6") (pin "5") (pinfunction "VEE_5") (pintype "passive"))
    )
    (net (code "14") (name "/EN") (class "Default")
      (node (ref "AND1") (pin "1") (pinfunction "A_1") (pintype "input"))
      (node (ref "AND2") (pin "1") (pinfunction "A_1") (pintype "input"))
      (node (ref "AND3") (pin "1") (pinfunction "A_1") (pintype "input"))
      (node (ref "AND4") (pin "1") (pinfunction "A_1") (pintype "input"))
      (node (ref "AND5") (pin "1") (pinfunction "A_1") (pintype "input"))
      (node (ref "AND6") (pin "1") (pinfunction "A_1") (pintype "input"))
    )
    (net (code "15") (name "/Gate_driver1") (class "Default")
      (node (ref "RG3") (pin "2") (pinfunction "2_2") (pintype "passive"))
    )
    (net (code "16") (name "/Gate_driver2") (class "Default")
      (node (ref "RG4") (pin "2") (pinfunction "2_2") (pintype "passive"))
    )
    (net (code "17") (name "/Gate_driver3") (class "Default")
      (node (ref "RG7") (pin "2") (pinfunction "2_2") (pintype "passive"))
    )
    (net (code "18") (name "/Gate_driver4") (class "Default")
      (node (ref "RG8") (pin "2") (pinfunction "2_2") (pintype "passive"))
    )
    (net (code "19") (name "/Gate_driver5") (class "Default")
      (node (ref "RG11") (pin "2") (pinfunction "2_2") (pintype "passive"))
    )
    (net (code "20") (name "/Gate_driver6") (class "Default")
      (node (ref "RG12") (pin "2") (pinfunction "2_2") (pintype "passive"))
    )
    (net (code "21") (name "/IN1") (class "Default")
      (node (ref "INVERSOR1") (pin "2") (pinfunction "A_2") (pintype "passive"))
      (node (ref "INVERSOR3") (pin "2") (pinfunction "A_2") (pintype "passive"))
    )
    (net (code "22") (name "/IN2") (class "Default")
      (node (ref "INVERSOR4") (pin "2") (pinfunction "A_2") (pintype "passive"))
      (node (ref "INVERSOR6") (pin "2") (pinfunction "A_2") (pintype "passive"))
    )
    (net (code "23") (name "/IN3") (class "Default")
      (node (ref "INVERSOR7") (pin "2") (pinfunction "A_2") (pintype "passive"))
      (node (ref "INVERSOR9") (pin "2") (pinfunction "A_2") (pintype "passive"))
    )
    (net (code "24") (name "GND") (class "Default")
      (node (ref "AND1") (pin "3") (pinfunction "GND_3") (pintype "power_in"))
      (node (ref "AND2") (pin "3") (pinfunction "GND_3") (pintype "power_in"))
      (node (ref "AND3") (pin "3") (pinfunction "GND_3") (pintype "power_in"))
      (node (ref "AND4") (pin "3") (pinfunction "GND_3") (pintype "power_in"))
      (node (ref "AND5") (pin "3") (pinfunction "GND_3") (pintype "power_in"))
      (node (ref "AND6") (pin "3") (pinfunction "GND_3") (pintype "power_in"))
      (node (ref "CG1") (pin "1") (pinfunction "1_1") (pintype "passive"))
      (node (ref "CG10") (pin "1") (pinfunction "1_1") (pintype "passive"))
      (node (ref "CG12") (pin "1") (pinfunction "1_1") (pintype "passive"))
      (node (ref "CG13") (pin "1") (pinfunction "1_1") (pintype "passive"))
      (node (ref "CG14") (pin "2") (pinfunction "2_2") (pintype "passive"))
      (node (ref "CG15") (pin "2") (pinfunction "2_2") (pintype "passive"))
      (node (ref "CG16") (pin "1") (pinfunction "1_1") (pintype "passive"))
      (node (ref "CG17") (pin "1") (pinfunction "1_1") (pintype "passive"))
      (node (ref "CG2") (pin "1") (pinfunction "1_1") (pintype "passive"))
      (node (ref "CG20") (pin "1") (pinfunction "1_1") (pintype "passive"))
      (node (ref "CG21") (pin "1") (pinfunction "1_1") (pintype "passive"))
      (node (ref "CG22") (pin "1") (pinfunction "1_1") (pintype "passive"))
      (node (ref "CG23") (pin "2") (pinfunction "2_2") (pintype "passive"))
      (node (ref "CG24") (pin "2") (pinfunction "2_2") (pintype "passive"))
      (node (ref "CG25") (pin "1") (pinfunction "1_1") (pintype "passive"))
      (node (ref "CG26") (pin "1") (pinfunction "1_1") (pintype "passive"))
      (node (ref "CG3") (pin "1") (pinfunction "1_1") (pintype "passive"))
      (node (ref "CG4") (pin "2") (pinfunction "2_2") (pintype "passive"))
      (node (ref "CG5") (pin "2") (pinfunction "2_2") (pintype "passive"))
      (node (ref "CG6") (pin "1") (pinfunction "1_1") (pintype "passive"))
      (node (ref "CG7") (pin "1") (pinfunction "1_1") (pintype "passive"))
      (node (ref "GD1") (pin "1") (pinfunction "N/C_1_1") (pintype "passive"))
      (node (ref "GD1") (pin "3") (pinfunction "CATHODE_3") (pintype "passive"))
      (node (ref "GD1") (pin "4") (pinfunction "N/C_2_4") (pintype "passive"))
      (node (ref "GD2") (pin "1") (pinfunction "N/C_1_1") (pintype "passive"))
      (node (ref "GD2") (pin "3") (pinfunction "CATHODE_3") (pintype "passive"))
      (node (ref "GD2") (pin "4") (pinfunction "N/C_2_4") (pintype "passive"))
      (node (ref "GD3") (pin "1") (pinfunction "N/C_1_1") (pintype "passive"))
      (node (ref "GD3") (pin "3") (pinfunction "CATHODE_3") (pintype "passive"))
      (node (ref "GD3") (pin "4") (pinfunction "N/C_2_4") (pintype "passive"))
      (node (ref "GD4") (pin "1") (pinfunction "N/C_1_1") (pintype "passive"))
      (node (ref "GD4") (pin "3") (pinfunction "CATHODE_3") (pintype "passive"))
      (node (ref "GD4") (pin "4") (pinfunction "N/C_2_4") (pintype "passive"))
      (node (ref "GD5") (pin "1") (pinfunction "N/C_1_1") (pintype "passive"))
      (node (ref "GD5") (pin "3") (pinfunction "CATHODE_3") (pintype "passive"))
      (node (ref "GD5") (pin "4") (pinfunction "N/C_2_4") (pintype "passive"))
      (node (ref "GD6") (pin "1") (pinfunction "N/C_1_1") (pintype "passive"))
      (node (ref "GD6") (pin "3") (pinfunction "CATHODE_3") (pintype "passive"))
      (node (ref "GD6") (pin "4") (pinfunction "N/C_2_4") (pintype "passive"))
      (node (ref "INVERSOR1") (pin "1") (pinfunction "NC_1") (pintype "passive"))
      (node (ref "INVERSOR1") (pin "3") (pinfunction "GND_3") (pintype "passive"))
      (node (ref "INVERSOR2") (pin "1") (pinfunction "NC_1") (pintype "passive"))
      (node (ref "INVERSOR2") (pin "3") (pinfunction "GND_3") (pintype "passive"))
      (node (ref "INVERSOR3") (pin "1") (pinfunction "NC_1") (pintype "passive"))
      (node (ref "INVERSOR3") (pin "3") (pinfunction "GND_3") (pintype "passive"))
      (node (ref "INVERSOR4") (pin "1") (pinfunction "NC_1") (pintype "passive"))
      (node (ref "INVERSOR4") (pin "3") (pinfunction "GND_3") (pintype "passive"))
      (node (ref "INVERSOR5") (pin "1") (pinfunction "NC_1") (pintype "passive"))
      (node (ref "INVERSOR5") (pin "3") (pinfunction "GND_3") (pintype "passive"))
      (node (ref "INVERSOR6") (pin "1") (pinfunction "NC_1") (pintype "passive"))
      (node (ref "INVERSOR6") (pin "3") (pinfunction "GND_3") (pintype "passive"))
      (node (ref "INVERSOR7") (pin "1") (pinfunction "NC_1") (pintype "passive"))
      (node (ref "INVERSOR7") (pin "3") (pinfunction "GND_3") (pintype "passive"))
      (node (ref "INVERSOR8") (pin "1") (pinfunction "NC_1") (pintype "passive"))
      (node (ref "INVERSOR8") (pin "3") (pinfunction "GND_3") (pintype "passive"))
      (node (ref "INVERSOR9") (pin "1") (pinfunction "NC_1") (pintype "passive"))
      (node (ref "INVERSOR9") (pin "3") (pinfunction "GND_3") (pintype "passive"))
    )
    (net (code "25") (name "Net-(AND1-B)") (class "Default")
      (node (ref "AND1") (pin "2") (pinfunction "B_2") (pintype "input"))
      (node (ref "CG4") (pin "1") (pinfunction "1_1") (pintype "passive"))
      (node (ref "DG1") (pin "2") (pinfunction "A_2") (pintype "passive"))
      (node (ref "TP19") (pin "1") (pinfunction "1_1") (pintype "passive"))
      (node (ref "TRIMMER1") (pin "2") (pinfunction "WIPER__2") (pintype "passive"))
      (node (ref "TRIMMER1") (pin "3") (pinfunction "CW_3") (pintype "passive"))
    )
    (net (code "26") (name "Net-(AND1-Y)") (class "Default")
      (node (ref "AND1") (pin "4") (pinfunction "Y_4") (pintype "output"))
      (node (ref "GD1") (pin "2") (pinfunction "ANODE_2") (pintype "passive"))
      (node (ref "RG1") (pin "1") (pinfunction "1_1") (pintype "passive"))
      (node (ref "TP20") (pin "1") (pinfunction "1_1") (pintype "passive"))
    )
    (net (code "27") (name "Net-(AND2-B)") (class "Default")
      (node (ref "AND2") (pin "2") (pinfunction "B_2") (pintype "input"))
      (node (ref "CG5") (pin "1") (pinfunction "1_1") (pintype "passive"))
      (node (ref "DG2") (pin "2") (pinfunction "A_2") (pintype "passive"))
      (node (ref "TP21") (pin "1") (pinfunction "1_1") (pintype "passive"))
      (node (ref "TRIMMER2") (pin "2") (pinfunction "WIPER__2") (pintype "passive"))
      (node (ref "TRIMMER2") (pin "3") (pinfunction "CW_3") (pintype "passive"))
    )
    (net (code "28") (name "Net-(AND2-Y)") (class "Default")
      (node (ref "AND2") (pin "4") (pinfunction "Y_4") (pintype "output"))
      (node (ref "GD2") (pin "2") (pinfunction "ANODE_2") (pintype "passive"))
      (node (ref "RG2") (pin "1") (pinfunction "1_1") (pintype "passive"))
      (node (ref "TP22") (pin "1") (pinfunction "1_1") (pintype "passive"))
    )
    (net (code "29") (name "Net-(AND3-B)") (class "Default")
      (node (ref "AND3") (pin "2") (pinfunction "B_2") (pintype "input"))
      (node (ref "CG14") (pin "1") (pinfunction "1_1") (pintype "passive"))
      (node (ref "DG3") (pin "2") (pinfunction "A_2") (pintype "passive"))
      (node (ref "TP23") (pin "1") (pinfunction "1_1") (pintype "passive"))
      (node (ref "TRIMMER3") (pin "2") (pinfunction "WIPER__2") (pintype "passive"))
      (node (ref "TRIMMER3") (pin "3") (pinfunction "CW_3") (pintype "passive"))
    )
    (net (code "30") (name "Net-(AND3-Y)") (class "Default")
      (node (ref "AND3") (pin "4") (pinfunction "Y_4") (pintype "output"))
      (node (ref "GD3") (pin "2") (pinfunction "ANODE_2") (pintype "passive"))
      (node (ref "RG5") (pin "1") (pinfunction "1_1") (pintype "passive"))
      (node (ref "TP24") (pin "1") (pinfunction "1_1") (pintype "passive"))
    )
    (net (code "31") (name "Net-(AND4-B)") (class "Default")
      (node (ref "AND4") (pin "2") (pinfunction "B_2") (pintype "input"))
      (node (ref "CG15") (pin "1") (pinfunction "1_1") (pintype "passive"))
      (node (ref "DG4") (pin "2") (pinfunction "A_2") (pintype "passive"))
      (node (ref "TP25") (pin "1") (pinfunction "1_1") (pintype "passive"))
      (node (ref "TRIMMER4") (pin "2") (pinfunction "WIPER__2") (pintype "passive"))
      (node (ref "TRIMMER4") (pin "3") (pinfunction "CW_3") (pintype "passive"))
    )
    (net (code "32") (name "Net-(AND4-Y)") (class "Default")
      (node (ref "AND4") (pin "4") (pinfunction "Y_4") (pintype "output"))
      (node (ref "GD4") (pin "2") (pinfunction "ANODE_2") (pintype "passive"))
      (node (ref "RG6") (pin "1") (pinfunction "1_1") (pintype "passive"))
      (node (ref "TP26") (pin "1") (pinfunction "1_1") (pintype "passive"))
    )
    (net (code "33") (name "Net-(AND5-B)") (class "Default")
      (node (ref "AND5") (pin "2") (pinfunction "B_2") (pintype "input"))
      (node (ref "CG23") (pin "1") (pinfunction "1_1") (pintype "passive"))
      (node (ref "DG5") (pin "2") (pinfunction "A_2") (pintype "passive"))
      (node (ref "TP27") (pin "1") (pinfunction "1_1") (pintype "passive"))
      (node (ref "TRIMMER5") (pin "2") (pinfunction "WIPER__2") (pintype "passive"))
      (node (ref "TRIMMER5") (pin "3") (pinfunction "CW_3") (pintype "passive"))
    )
    (net (code "34") (name "Net-(AND5-Y)") (class "Default")
      (node (ref "AND5") (pin "4") (pinfunction "Y_4") (pintype "output"))
      (node (ref "GD5") (pin "2") (pinfunction "ANODE_2") (pintype "passive"))
      (node (ref "RG9") (pin "1") (pinfunction "1_1") (pintype "passive"))
      (node (ref "TP28") (pin "1") (pinfunction "1_1") (pintype "passive"))
    )
    (net (code "35") (name "Net-(AND6-B)") (class "Default")
      (node (ref "AND6") (pin "2") (pinfunction "B_2") (pintype "input"))
      (node (ref "CG24") (pin "1") (pinfunction "1_1") (pintype "passive"))
      (node (ref "DG6") (pin "2") (pinfunction "A_2") (pintype "passive"))
      (node (ref "TP29") (pin "1") (pinfunction "1_1") (pintype "passive"))
      (node (ref "TRIMMER6") (pin "2") (pinfunction "WIPER__2") (pintype "passive"))
      (node (ref "TRIMMER6") (pin "3") (pinfunction "CW_3") (pintype "passive"))
    )
    (net (code "36") (name "Net-(AND6-Y)") (class "Default")
      (node (ref "AND6") (pin "4") (pinfunction "Y_4") (pintype "output"))
      (node (ref "GD6") (pin "2") (pinfunction "ANODE_2") (pintype "passive"))
      (node (ref "RG10") (pin "1") (pinfunction "1_1") (pintype "passive"))
      (node (ref "TP30") (pin "1") (pinfunction "1_1") (pintype "passive"))
    )
    (net (code "37") (name "Net-(DG1-K)") (class "Default")
      (node (ref "DG1") (pin "1") (pinfunction "K_1") (pintype "passive"))
      (node (ref "INVERSOR2") (pin "4") (pinfunction "Y_4") (pintype "passive"))
      (node (ref "TRIMMER1") (pin "1") (pinfunction "CCW_1") (pintype "passive"))
    )
    (net (code "38") (name "Net-(DG2-K)") (class "Default")
      (node (ref "DG2") (pin "1") (pinfunction "K_1") (pintype "passive"))
      (node (ref "INVERSOR3") (pin "4") (pinfunction "Y_4") (pintype "passive"))
      (node (ref "TRIMMER2") (pin "1") (pinfunction "CCW_1") (pintype "passive"))
    )
    (net (code "39") (name "Net-(DG3-K)") (class "Default")
      (node (ref "DG3") (pin "1") (pinfunction "K_1") (pintype "passive"))
      (node (ref "INVERSOR5") (pin "4") (pinfunction "Y_4") (pintype "passive"))
      (node (ref "TRIMMER3") (pin "1") (pinfunction "CCW_1") (pintype "passive"))
    )
    (net (code "40") (name "Net-(DG4-K)") (class "Default")
      (node (ref "DG4") (pin "1") (pinfunction "K_1") (pintype "passive"))
      (node (ref "INVERSOR6") (pin "4") (pinfunction "Y_4") (pintype "passive"))
      (node (ref "TRIMMER4") (pin "1") (pinfunction "CCW_1") (pintype "passive"))
    )
    (net (code "41") (name "Net-(DG5-K)") (class "Default")
      (node (ref "DG5") (pin "1") (pinfunction "K_1") (pintype "passive"))
      (node (ref "INVERSOR8") (pin "4") (pinfunction "Y_4") (pintype "passive"))
      (node (ref "TRIMMER5") (pin "1") (pinfunction "CCW_1") (pintype "passive"))
    )
    (net (code "42") (name "Net-(DG6-K)") (class "Default")
      (node (ref "DG6") (pin "1") (pinfunction "K_1") (pintype "passive"))
      (node (ref "INVERSOR9") (pin "4") (pinfunction "Y_4") (pintype "passive"))
      (node (ref "TRIMMER6") (pin "1") (pinfunction "CCW_1") (pintype "passive"))
    )
    (net (code "43") (name "Net-(GD1-VO_1)") (class "Default")
      (node (ref "GD1") (pin "6") (pinfunction "VO_1_6") (pintype "passive"))
      (node (ref "GD1") (pin "7") (pinfunction "VO_2_7") (pintype "passive"))
      (node (ref "RG3") (pin "1") (pinfunction "1_1") (pintype "passive"))
    )
    (net (code "44") (name "Net-(GD2-VO_1)") (class "Default")
      (node (ref "GD2") (pin "6") (pinfunction "VO_1_6") (pintype "passive"))
      (node (ref "GD2") (pin "7") (pinfunction "VO_2_7") (pintype "passive"))
      (node (ref "RG4") (pin "1") (pinfunction "1_1") (pintype "passive"))
    )
    (net (code "45") (name "Net-(GD3-VO_1)") (class "Default")
      (node (ref "GD3") (pin "6") (pinfunction "VO_1_6") (pintype "passive"))
      (node (ref "GD3") (pin "7") (pinfunction "VO_2_7") (pintype "passive"))
      (node (ref "RG7") (pin "1") (pinfunction "1_1") (pintype "passive"))
    )
    (net (code "46") (name "Net-(GD4-VO_1)") (class "Default")
      (node (ref "GD4") (pin "6") (pinfunction "VO_1_6") (pintype "passive"))
      (node (ref "GD4") (pin "7") (pinfunction "VO_2_7") (pintype "passive"))
      (node (ref "RG8") (pin "1") (pinfunction "1_1") (pintype "passive"))
    )
    (net (code "47") (name "Net-(GD5-VO_1)") (class "Default")
      (node (ref "GD5") (pin "6") (pinfunction "VO_1_6") (pintype "passive"))
      (node (ref "GD5") (pin "7") (pinfunction "VO_2_7") (pintype "passive"))
      (node (ref "RG11") (pin "1") (pinfunction "1_1") (pintype "passive"))
    )
    (net (code "48") (name "Net-(GD6-VO_1)") (class "Default")
      (node (ref "GD6") (pin "6") (pinfunction "VO_1_6") (pintype "passive"))
      (node (ref "GD6") (pin "7") (pinfunction "VO_2_7") (pintype "passive"))
      (node (ref "RG12") (pin "1") (pinfunction "1_1") (pintype "passive"))
    )
    (net (code "49") (name "Net-(INVERSOR1-Y)") (class "Default")
      (node (ref "INVERSOR1") (pin "4") (pinfunction "Y_4") (pintype "passive"))
      (node (ref "INVERSOR2") (pin "2") (pinfunction "A_2") (pintype "passive"))
    )
    (net (code "50") (name "Net-(INVERSOR4-Y)") (class "Default")
      (node (ref "INVERSOR4") (pin "4") (pinfunction "Y_4") (pintype "passive"))
      (node (ref "INVERSOR5") (pin "2") (pinfunction "A_2") (pintype "passive"))
    )
    (net (code "51") (name "Net-(INVERSOR7-Y)") (class "Default")
      (node (ref "INVERSOR7") (pin "4") (pinfunction "Y_4") (pintype "passive"))
      (node (ref "INVERSOR8") (pin "2") (pinfunction "A_2") (pintype "passive"))
    )
  )
)
